# bredtoob.net
KiCad netlist of a schematic drawn in EAGLE
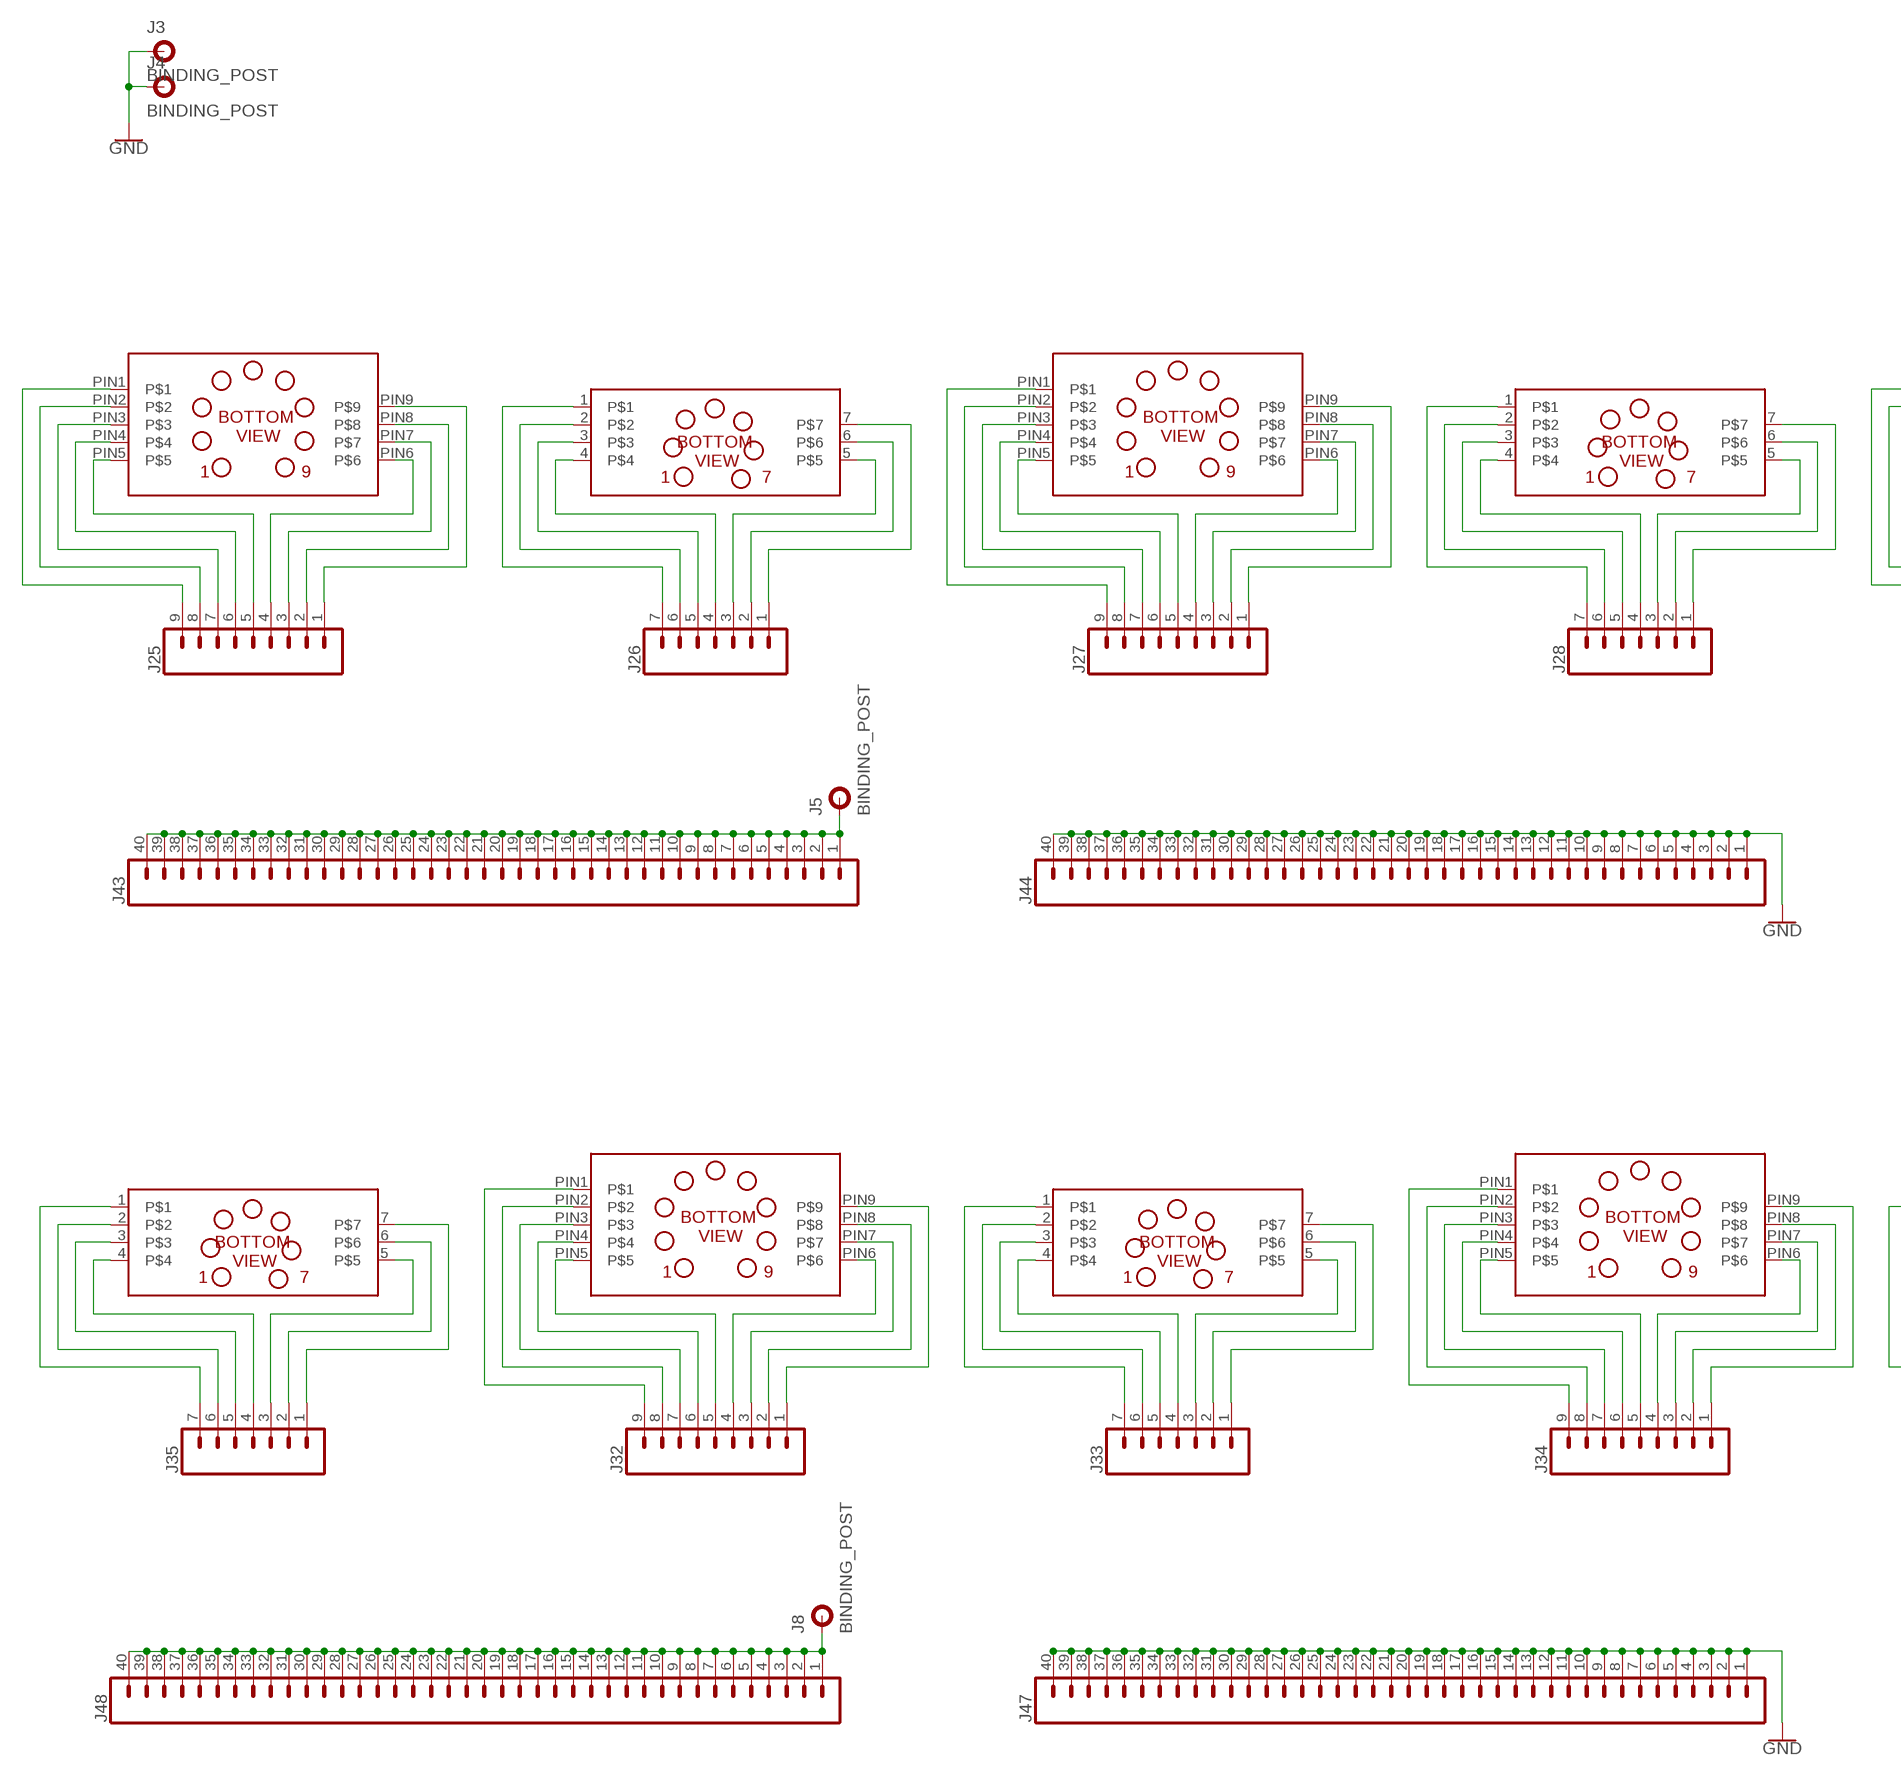
[diagram p0: schematic, sheet 1, part 1 of 2]
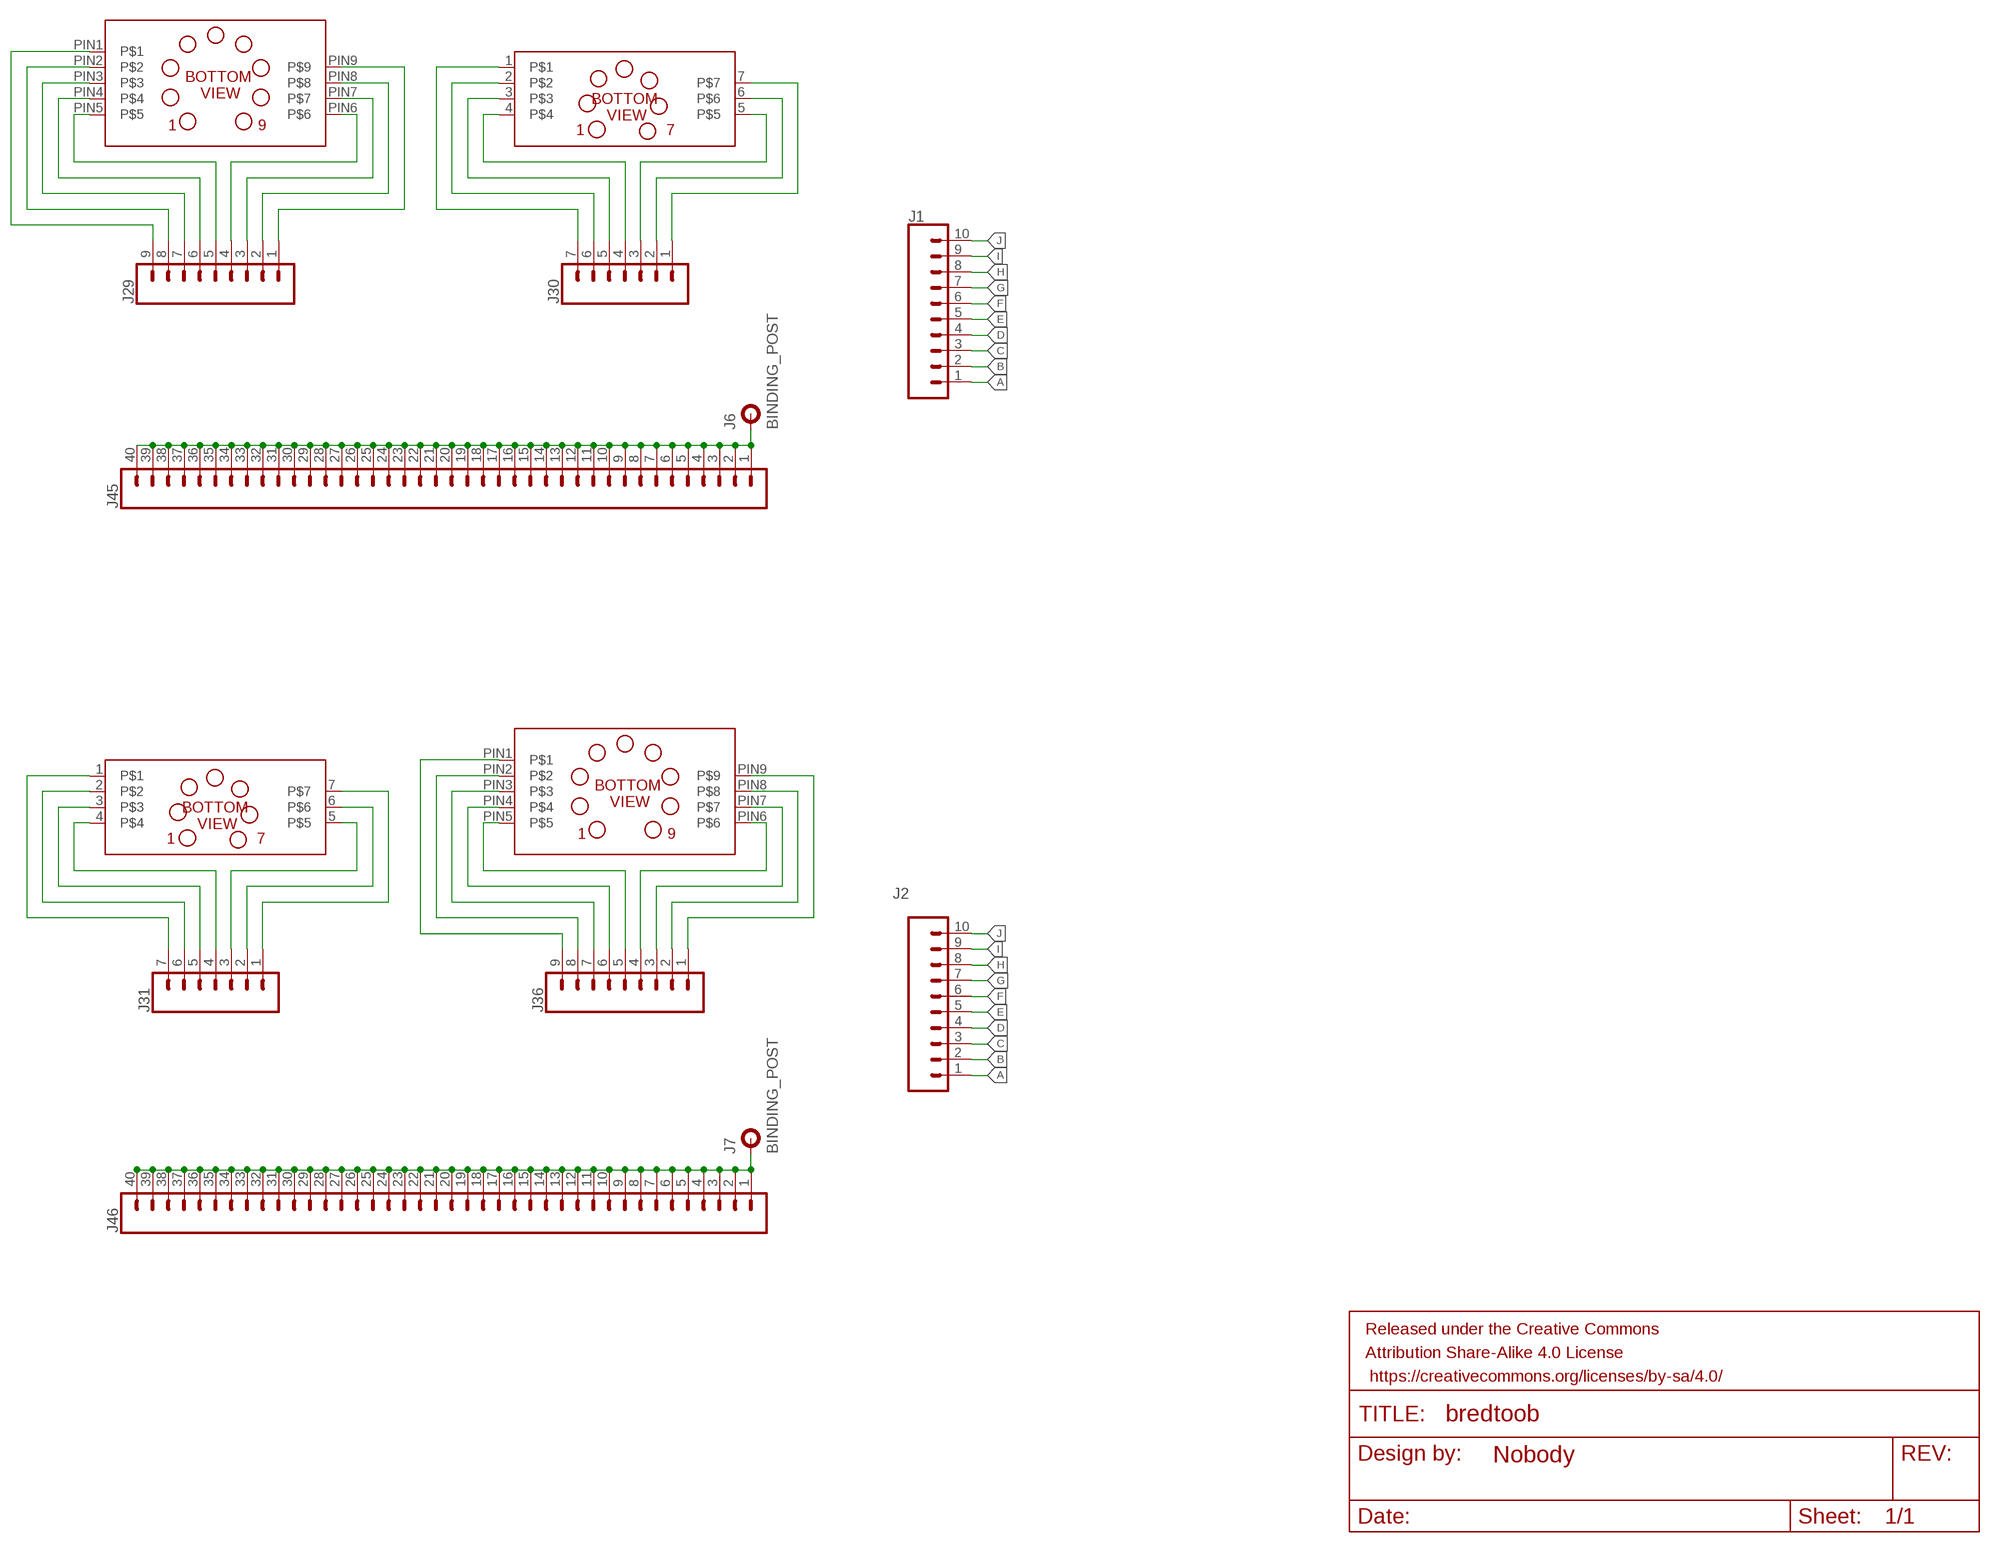
[diagram p1: schematic, sheet 1, part 2 of 2]

(export (version "E")
  (design (tool "Eeschema 10.0.6"))
  (components
    (comp (ref "FRAME1")
      (value "FRAME-LETTERNO_PACKAGE")
      (footprint "eagle-import:DUMMY")
      (fields (field (name "DESIGNER") "Nobody"))
      (libsource (lib "eagle-import") (part "FRAME-LETTERNO_PACKAGE"))
    )
    (comp (ref "J1")
      (value "CONN_10NO_SILK_PTH_FEMALE")
      (footprint "eagle-import:1X10_NO_SILK")
      (libsource (lib "eagle-import") (part "CONN_10NO_SILK_PTH_FEMALE"))
    )
    (comp (ref "J2")
      (value "CONN_10NO_SILK_PTH_FEMALE")
      (footprint "eagle-import:1X10_NO_SILK")
      (libsource (lib "eagle-import") (part "CONN_10NO_SILK_PTH_FEMALE"))
    )
    (comp (ref "J3")
      (value "BINDING_POST")
      (footprint "eagle-import:BINDING_POST")
      (libsource (lib "eagle-import") (part "BINDING_POST"))
    )
    (comp (ref "J4")
      (value "BINDING_POST")
      (footprint "eagle-import:BINDING_POST")
      (libsource (lib "eagle-import") (part "BINDING_POST"))
    )
    (comp (ref "J5")
      (value "BINDING_POST")
      (footprint "eagle-import:BINDING_POST")
      (libsource (lib "eagle-import") (part "BINDING_POST"))
    )
    (comp (ref "J6")
      (value "BINDING_POST")
      (footprint "eagle-import:BINDING_POST")
      (libsource (lib "eagle-import") (part "BINDING_POST"))
    )
    (comp (ref "J7")
      (value "BINDING_POST")
      (footprint "eagle-import:BINDING_POST")
      (libsource (lib "eagle-import") (part "BINDING_POST"))
    )
    (comp (ref "J8")
      (value "BINDING_POST")
      (footprint "eagle-import:BINDING_POST")
      (libsource (lib "eagle-import") (part "BINDING_POST"))
    )
    (comp (ref "J25")
      (value "CONN_09")
      (footprint "eagle-import:1X09")
      (libsource (lib "eagle-import") (part "CONN_09"))
    )
    (comp (ref "J26")
      (value "CONN_07NO_SILK")
      (footprint "eagle-import:1X07_NO_SILK")
      (libsource (lib "eagle-import") (part "CONN_07NO_SILK"))
    )
    (comp (ref "J27")
      (value "CONN_09")
      (footprint "eagle-import:1X09")
      (libsource (lib "eagle-import") (part "CONN_09"))
    )
    (comp (ref "J28")
      (value "CONN_07NO_SILK")
      (footprint "eagle-import:1X07_NO_SILK")
      (libsource (lib "eagle-import") (part "CONN_07NO_SILK"))
    )
    (comp (ref "J29")
      (value "CONN_09")
      (footprint "eagle-import:1X09")
      (libsource (lib "eagle-import") (part "CONN_09"))
    )
    (comp (ref "J30")
      (value "CONN_07NO_SILK")
      (footprint "eagle-import:1X07_NO_SILK")
      (libsource (lib "eagle-import") (part "CONN_07NO_SILK"))
    )
    (comp (ref "J31")
      (value "CONN_07NO_SILK")
      (footprint "eagle-import:1X07_NO_SILK")
      (libsource (lib "eagle-import") (part "CONN_07NO_SILK"))
    )
    (comp (ref "J32")
      (value "CONN_09")
      (footprint "eagle-import:1X09")
      (libsource (lib "eagle-import") (part "CONN_09"))
    )
    (comp (ref "J33")
      (value "CONN_07NO_SILK")
      (footprint "eagle-import:1X07_NO_SILK")
      (libsource (lib "eagle-import") (part "CONN_07NO_SILK"))
    )
    (comp (ref "J34")
      (value "CONN_09")
      (footprint "eagle-import:1X09")
      (libsource (lib "eagle-import") (part "CONN_09"))
    )
    (comp (ref "J35")
      (value "CONN_07NO_SILK")
      (footprint "eagle-import:1X07_NO_SILK")
      (libsource (lib "eagle-import") (part "CONN_07NO_SILK"))
    )
    (comp (ref "J36")
      (value "CONN_09")
      (footprint "eagle-import:1X09")
      (libsource (lib "eagle-import") (part "CONN_09"))
    )
    (comp (ref "J43")
      (value "CONN_40")
      (footprint "eagle-import:1X40")
      (libsource (lib "eagle-import") (part "CONN_40"))
    )
    (comp (ref "J44")
      (value "CONN_40")
      (footprint "eagle-import:1X40")
      (libsource (lib "eagle-import") (part "CONN_40"))
    )
    (comp (ref "J45")
      (value "CONN_40")
      (footprint "eagle-import:1X40")
      (libsource (lib "eagle-import") (part "CONN_40"))
    )
    (comp (ref "J46")
      (value "CONN_40")
      (footprint "eagle-import:1X40")
      (libsource (lib "eagle-import") (part "CONN_40"))
    )
    (comp (ref "J47")
      (value "CONN_40")
      (footprint "eagle-import:1X40")
      (libsource (lib "eagle-import") (part "CONN_40"))
    )
    (comp (ref "J48")
      (value "CONN_40")
      (footprint "eagle-import:1X40")
      (libsource (lib "eagle-import") (part "CONN_40"))
    )
    (comp (ref "U$1")
      (value "9PINMINI")
      (footprint "eagle-import:9-PIN-MINIATURE")
      (libsource (lib "eagle-import") (part "9PINMINI"))
    )
    (comp (ref "U$2")
      (value "7PINMINI")
      (footprint "eagle-import:7-PIN-MINIATURE(B7G)")
      (libsource (lib "eagle-import") (part "7PINMINI"))
    )
    (comp (ref "U$3")
      (value "9PINMINI")
      (footprint "eagle-import:9-PIN-MINIATURE")
      (libsource (lib "eagle-import") (part "9PINMINI"))
    )
    (comp (ref "U$4")
      (value "7PINMINI")
      (footprint "eagle-import:7-PIN-MINIATURE(B7G)")
      (libsource (lib "eagle-import") (part "7PINMINI"))
    )
    (comp (ref "U$5")
      (value "9PINMINI")
      (footprint "eagle-import:9-PIN-MINIATURE")
      (libsource (lib "eagle-import") (part "9PINMINI"))
    )
    (comp (ref "U$6")
      (value "7PINMINI")
      (footprint "eagle-import:7-PIN-MINIATURE(B7G)")
      (libsource (lib "eagle-import") (part "7PINMINI"))
    )
    (comp (ref "U$7")
      (value "7PINMINI")
      (footprint "eagle-import:7-PIN-MINIATURE(B7G)")
      (libsource (lib "eagle-import") (part "7PINMINI"))
    )
    (comp (ref "U$8")
      (value "9PINMINI")
      (footprint "eagle-import:9-PIN-MINIATURE")
      (libsource (lib "eagle-import") (part "9PINMINI"))
    )
    (comp (ref "U$9")
      (value "7PINMINI")
      (footprint "eagle-import:7-PIN-MINIATURE(B7G)")
      (libsource (lib "eagle-import") (part "7PINMINI"))
    )
    (comp (ref "U$10")
      (value "9PINMINI")
      (footprint "eagle-import:9-PIN-MINIATURE")
      (libsource (lib "eagle-import") (part "9PINMINI"))
    )
    (comp (ref "U$11")
      (value "7PINMINI")
      (footprint "eagle-import:7-PIN-MINIATURE(B7G)")
      (libsource (lib "eagle-import") (part "7PINMINI"))
    )
    (comp (ref "U$12")
      (value "9PINMINI")
      (footprint "eagle-import:9-PIN-MINIATURE")
      (libsource (lib "eagle-import") (part "9PINMINI"))
    )
  )
  (nets
    (net (code "1") (name "A") (class "Default")
      (node (ref "J1") (pin "1") (pinfunction "1_1") (pintype "passive"))
      (node (ref "J2") (pin "1") (pinfunction "1_1") (pintype "passive"))
    )
    (net (code "2") (name "B") (class "Default")
      (node (ref "J1") (pin "2") (pinfunction "2_2") (pintype "passive"))
      (node (ref "J2") (pin "2") (pinfunction "2_2") (pintype "passive"))
    )
    (net (code "3") (name "C") (class "Default")
      (node (ref "J1") (pin "3") (pinfunction "3_3") (pintype "passive"))
      (node (ref "J2") (pin "3") (pinfunction "3_3") (pintype "passive"))
    )
    (net (code "4") (name "D") (class "Default")
      (node (ref "J1") (pin "4") (pinfunction "4_4") (pintype "passive"))
      (node (ref "J2") (pin "4") (pinfunction "4_4") (pintype "passive"))
    )
    (net (code "5") (name "E") (class "Default")
      (node (ref "J1") (pin "5") (pinfunction "5_5") (pintype "passive"))
      (node (ref "J2") (pin "5") (pinfunction "5_5") (pintype "passive"))
    )
    (net (code "6") (name "F") (class "Default")
      (node (ref "J1") (pin "6") (pinfunction "6_6") (pintype "passive"))
      (node (ref "J2") (pin "6") (pinfunction "6_6") (pintype "passive"))
    )
    (net (code "7") (name "G") (class "Default")
      (node (ref "J1") (pin "7") (pinfunction "7_7") (pintype "passive"))
      (node (ref "J2") (pin "7") (pinfunction "7_7") (pintype "passive"))
    )
    (net (code "8") (name "GND") (class "Default")
      (node (ref "J3") (pin "P$1") (pinfunction "P$1_P$1") (pintype "bidirectional"))
      (node (ref "J4") (pin "P$1") (pinfunction "P$1_P$1") (pintype "bidirectional"))
      (node (ref "J44") (pin "1") (pinfunction "1_1") (pintype "passive"))
      (node (ref "J44") (pin "10") (pinfunction "10_10") (pintype "passive"))
      (node (ref "J44") (pin "11") (pinfunction "11_11") (pintype "passive"))
      (node (ref "J44") (pin "12") (pinfunction "12_12") (pintype "passive"))
      (node (ref "J44") (pin "13") (pinfunction "13_13") (pintype "passive"))
      (node (ref "J44") (pin "14") (pinfunction "14_14") (pintype "passive"))
      (node (ref "J44") (pin "15") (pinfunction "15_15") (pintype "passive"))
      (node (ref "J44") (pin "16") (pinfunction "16_16") (pintype "passive"))
      (node (ref "J44") (pin "17") (pinfunction "17_17") (pintype "passive"))
      (node (ref "J44") (pin "18") (pinfunction "18_18") (pintype "passive"))
      (node (ref "J44") (pin "19") (pinfunction "19_19") (pintype "passive"))
      (node (ref "J44") (pin "2") (pinfunction "2_2") (pintype "passive"))
      (node (ref "J44") (pin "20") (pinfunction "20_20") (pintype "passive"))
      (node (ref "J44") (pin "21") (pinfunction "21_21") (pintype "passive"))
      (node (ref "J44") (pin "22") (pinfunction "22_22") (pintype "passive"))
      (node (ref "J44") (pin "23") (pinfunction "23_23") (pintype "passive"))
      (node (ref "J44") (pin "24") (pinfunction "24_24") (pintype "passive"))
      (node (ref "J44") (pin "25") (pinfunction "25_25") (pintype "passive"))
      (node (ref "J44") (pin "26") (pinfunction "26_26") (pintype "passive"))
      (node (ref "J44") (pin "27") (pinfunction "27_27") (pintype "passive"))
      (node (ref "J44") (pin "28") (pinfunction "28_28") (pintype "passive"))
      (node (ref "J44") (pin "29") (pinfunction "29_29") (pintype "passive"))
      (node (ref "J44") (pin "3") (pinfunction "3_3") (pintype "passive"))
      (node (ref "J44") (pin "30") (pinfunction "30_30") (pintype "passive"))
      (node (ref "J44") (pin "31") (pinfunction "31_31") (pintype "passive"))
      (node (ref "J44") (pin "32") (pinfunction "32_32") (pintype "passive"))
      (node (ref "J44") (pin "33") (pinfunction "33_33") (pintype "passive"))
      (node (ref "J44") (pin "34") (pinfunction "34_34") (pintype "passive"))
      (node (ref "J44") (pin "35") (pinfunction "35_35") (pintype "passive"))
      (node (ref "J44") (pin "36") (pinfunction "36_36") (pintype "passive"))
      (node (ref "J44") (pin "37") (pinfunction "37_37") (pintype "passive"))
      (node (ref "J44") (pin "38") (pinfunction "38_38") (pintype "passive"))
      (node (ref "J44") (pin "39") (pinfunction "39_39") (pintype "passive"))
      (node (ref "J44") (pin "4") (pinfunction "4_4") (pintype "passive"))
      (node (ref "J44") (pin "40") (pinfunction "40_40") (pintype "passive"))
      (node (ref "J44") (pin "5") (pinfunction "5_5") (pintype "passive"))
      (node (ref "J44") (pin "6") (pinfunction "6_6") (pintype "passive"))
      (node (ref "J44") (pin "7") (pinfunction "7_7") (pintype "passive"))
      (node (ref "J44") (pin "8") (pinfunction "8_8") (pintype "passive"))
      (node (ref "J44") (pin "9") (pinfunction "9_9") (pintype "passive"))
      (node (ref "J47") (pin "1") (pinfunction "1_1") (pintype "passive"))
      (node (ref "J47") (pin "10") (pinfunction "10_10") (pintype "passive"))
      (node (ref "J47") (pin "11") (pinfunction "11_11") (pintype "passive"))
      (node (ref "J47") (pin "12") (pinfunction "12_12") (pintype "passive"))
      (node (ref "J47") (pin "13") (pinfunction "13_13") (pintype "passive"))
      (node (ref "J47") (pin "14") (pinfunction "14_14") (pintype "passive"))
      (node (ref "J47") (pin "15") (pinfunction "15_15") (pintype "passive"))
      (node (ref "J47") (pin "16") (pinfunction "16_16") (pintype "passive"))
      (node (ref "J47") (pin "17") (pinfunction "17_17") (pintype "passive"))
      (node (ref "J47") (pin "18") (pinfunction "18_18") (pintype "passive"))
      (node (ref "J47") (pin "19") (pinfunction "19_19") (pintype "passive"))
      (node (ref "J47") (pin "2") (pinfunction "2_2") (pintype "passive"))
      (node (ref "J47") (pin "20") (pinfunction "20_20") (pintype "passive"))
      (node (ref "J47") (pin "21") (pinfunction "21_21") (pintype "passive"))
      (node (ref "J47") (pin "22") (pinfunction "22_22") (pintype "passive"))
      (node (ref "J47") (pin "23") (pinfunction "23_23") (pintype "passive"))
      (node (ref "J47") (pin "24") (pinfunction "24_24") (pintype "passive"))
      (node (ref "J47") (pin "25") (pinfunction "25_25") (pintype "passive"))
      (node (ref "J47") (pin "26") (pinfunction "26_26") (pintype "passive"))
      (node (ref "J47") (pin "27") (pinfunction "27_27") (pintype "passive"))
      (node (ref "J47") (pin "28") (pinfunction "28_28") (pintype "passive"))
      (node (ref "J47") (pin "29") (pinfunction "29_29") (pintype "passive"))
      (node (ref "J47") (pin "3") (pinfunction "3_3") (pintype "passive"))
      (node (ref "J47") (pin "30") (pinfunction "30_30") (pintype "passive"))
      (node (ref "J47") (pin "31") (pinfunction "31_31") (pintype "passive"))
      (node (ref "J47") (pin "32") (pinfunction "32_32") (pintype "passive"))
      (node (ref "J47") (pin "33") (pinfunction "33_33") (pintype "passive"))
      (node (ref "J47") (pin "34") (pinfunction "34_34") (pintype "passive"))
      (node (ref "J47") (pin "35") (pinfunction "35_35") (pintype "passive"))
      (node (ref "J47") (pin "36") (pinfunction "36_36") (pintype "passive"))
      (node (ref "J47") (pin "37") (pinfunction "37_37") (pintype "passive"))
      (node (ref "J47") (pin "38") (pinfunction "38_38") (pintype "passive"))
      (node (ref "J47") (pin "39") (pinfunction "39_39") (pintype "passive"))
      (node (ref "J47") (pin "4") (pinfunction "4_4") (pintype "passive"))
      (node (ref "J47") (pin "40") (pinfunction "40_40") (pintype "passive"))
      (node (ref "J47") (pin "5") (pinfunction "5_5") (pintype "passive"))
      (node (ref "J47") (pin "6") (pinfunction "6_6") (pintype "passive"))
      (node (ref "J47") (pin "7") (pinfunction "7_7") (pintype "passive"))
      (node (ref "J47") (pin "8") (pinfunction "8_8") (pintype "passive"))
      (node (ref "J47") (pin "9") (pinfunction "9_9") (pintype "passive"))
    )
    (net (code "9") (name "H") (class "Default")
      (node (ref "J1") (pin "8") (pinfunction "8_8") (pintype "passive"))
      (node (ref "J2") (pin "8") (pinfunction "8_8") (pintype "passive"))
    )
    (net (code "10") (name "I") (class "Default")
      (node (ref "J1") (pin "9") (pinfunction "9_9") (pintype "passive"))
      (node (ref "J2") (pin "9") (pinfunction "9_9") (pintype "passive"))
    )
    (net (code "11") (name "J") (class "Default")
      (node (ref "J1") (pin "10") (pinfunction "10_10") (pintype "passive"))
      (node (ref "J2") (pin "10") (pinfunction "10_10") (pintype "passive"))
    )
    (net (code "12") (name "Net-(J43-Pad1)") (class "Default")
      (node (ref "J43") (pin "1") (pinfunction "1_1") (pintype "passive"))
      (node (ref "J43") (pin "10") (pinfunction "10_10") (pintype "passive"))
      (node (ref "J43") (pin "11") (pinfunction "11_11") (pintype "passive"))
      (node (ref "J43") (pin "12") (pinfunction "12_12") (pintype "passive"))
      (node (ref "J43") (pin "13") (pinfunction "13_13") (pintype "passive"))
      (node (ref "J43") (pin "14") (pinfunction "14_14") (pintype "passive"))
      (node (ref "J43") (pin "15") (pinfunction "15_15") (pintype "passive"))
      (node (ref "J43") (pin "16") (pinfunction "16_16") (pintype "passive"))
      (node (ref "J43") (pin "17") (pinfunction "17_17") (pintype "passive"))
      (node (ref "J43") (pin "18") (pinfunction "18_18") (pintype "passive"))
      (node (ref "J43") (pin "19") (pinfunction "19_19") (pintype "passive"))
      (node (ref "J43") (pin "2") (pinfunction "2_2") (pintype "passive"))
      (node (ref "J43") (pin "20") (pinfunction "20_20") (pintype "passive"))
      (node (ref "J43") (pin "21") (pinfunction "21_21") (pintype "passive"))
      (node (ref "J43") (pin "22") (pinfunction "22_22") (pintype "passive"))
      (node (ref "J43") (pin "23") (pinfunction "23_23") (pintype "passive"))
      (node (ref "J43") (pin "24") (pinfunction "24_24") (pintype "passive"))
      (node (ref "J43") (pin "25") (pinfunction "25_25") (pintype "passive"))
      (node (ref "J43") (pin "26") (pinfunction "26_26") (pintype "passive"))
      (node (ref "J43") (pin "27") (pinfunction "27_27") (pintype "passive"))
      (node (ref "J43") (pin "28") (pinfunction "28_28") (pintype "passive"))
      (node (ref "J43") (pin "29") (pinfunction "29_29") (pintype "passive"))
      (node (ref "J43") (pin "3") (pinfunction "3_3") (pintype "passive"))
      (node (ref "J43") (pin "30") (pinfunction "30_30") (pintype "passive"))
      (node (ref "J43") (pin "31") (pinfunction "31_31") (pintype "passive"))
      (node (ref "J43") (pin "32") (pinfunction "32_32") (pintype "passive"))
      (node (ref "J43") (pin "33") (pinfunction "33_33") (pintype "passive"))
      (node (ref "J43") (pin "34") (pinfunction "34_34") (pintype "passive"))
      (node (ref "J43") (pin "35") (pinfunction "35_35") (pintype "passive"))
      (node (ref "J43") (pin "36") (pinfunction "36_36") (pintype "passive"))
      (node (ref "J43") (pin "37") (pinfunction "37_37") (pintype "passive"))
      (node (ref "J43") (pin "38") (pinfunction "38_38") (pintype "passive"))
      (node (ref "J43") (pin "39") (pinfunction "39_39") (pintype "passive"))
      (node (ref "J43") (pin "4") (pinfunction "4_4") (pintype "passive"))
      (node (ref "J43") (pin "40") (pinfunction "40_40") (pintype "passive"))
      (node (ref "J43") (pin "5") (pinfunction "5_5") (pintype "passive"))
      (node (ref "J43") (pin "6") (pinfunction "6_6") (pintype "passive"))
      (node (ref "J43") (pin "7") (pinfunction "7_7") (pintype "passive"))
      (node (ref "J43") (pin "8") (pinfunction "8_8") (pintype "passive"))
      (node (ref "J43") (pin "9") (pinfunction "9_9") (pintype "passive"))
      (node (ref "J5") (pin "P$1") (pinfunction "P$1_P$1") (pintype "bidirectional"))
    )
    (net (code "13") (name "Net-(J45-Pad1)") (class "Default")
      (node (ref "J45") (pin "1") (pinfunction "1_1") (pintype "passive"))
      (node (ref "J45") (pin "10") (pinfunction "10_10") (pintype "passive"))
      (node (ref "J45") (pin "11") (pinfunction "11_11") (pintype "passive"))
      (node (ref "J45") (pin "12") (pinfunction "12_12") (pintype "passive"))
      (node (ref "J45") (pin "13") (pinfunction "13_13") (pintype "passive"))
      (node (ref "J45") (pin "14") (pinfunction "14_14") (pintype "passive"))
      (node (ref "J45") (pin "15") (pinfunction "15_15") (pintype "passive"))
      (node (ref "J45") (pin "16") (pinfunction "16_16") (pintype "passive"))
      (node (ref "J45") (pin "17") (pinfunction "17_17") (pintype "passive"))
      (node (ref "J45") (pin "18") (pinfunction "18_18") (pintype "passive"))
      (node (ref "J45") (pin "19") (pinfunction "19_19") (pintype "passive"))
      (node (ref "J45") (pin "2") (pinfunction "2_2") (pintype "passive"))
      (node (ref "J45") (pin "20") (pinfunction "20_20") (pintype "passive"))
      (node (ref "J45") (pin "21") (pinfunction "21_21") (pintype "passive"))
      (node (ref "J45") (pin "22") (pinfunction "22_22") (pintype "passive"))
      (node (ref "J45") (pin "23") (pinfunction "23_23") (pintype "passive"))
      (node (ref "J45") (pin "24") (pinfunction "24_24") (pintype "passive"))
      (node (ref "J45") (pin "25") (pinfunction "25_25") (pintype "passive"))
      (node (ref "J45") (pin "26") (pinfunction "26_26") (pintype "passive"))
      (node (ref "J45") (pin "27") (pinfunction "27_27") (pintype "passive"))
      (node (ref "J45") (pin "28") (pinfunction "28_28") (pintype "passive"))
      (node (ref "J45") (pin "29") (pinfunction "29_29") (pintype "passive"))
      (node (ref "J45") (pin "3") (pinfunction "3_3") (pintype "passive"))
      (node (ref "J45") (pin "30") (pinfunction "30_30") (pintype "passive"))
      (node (ref "J45") (pin "31") (pinfunction "31_31") (pintype "passive"))
      (node (ref "J45") (pin "32") (pinfunction "32_32") (pintype "passive"))
      (node (ref "J45") (pin "33") (pinfunction "33_33") (pintype "passive"))
      (node (ref "J45") (pin "34") (pinfunction "34_34") (pintype "passive"))
      (node (ref "J45") (pin "35") (pinfunction "35_35") (pintype "passive"))
      (node (ref "J45") (pin "36") (pinfunction "36_36") (pintype "passive"))
      (node (ref "J45") (pin "37") (pinfunction "37_37") (pintype "passive"))
      (node (ref "J45") (pin "38") (pinfunction "38_38") (pintype "passive"))
      (node (ref "J45") (pin "39") (pinfunction "39_39") (pintype "passive"))
      (node (ref "J45") (pin "4") (pinfunction "4_4") (pintype "passive"))
      (node (ref "J45") (pin "40") (pinfunction "40_40") (pintype "passive"))
      (node (ref "J45") (pin "5") (pinfunction "5_5") (pintype "passive"))
      (node (ref "J45") (pin "6") (pinfunction "6_6") (pintype "passive"))
      (node (ref "J45") (pin "7") (pinfunction "7_7") (pintype "passive"))
      (node (ref "J45") (pin "8") (pinfunction "8_8") (pintype "passive"))
      (node (ref "J45") (pin "9") (pinfunction "9_9") (pintype "passive"))
      (node (ref "J6") (pin "P$1") (pinfunction "P$1_P$1") (pintype "bidirectional"))
    )
    (net (code "14") (name "Net-(J46-Pad1)") (class "Default")
      (node (ref "J46") (pin "1") (pinfunction "1_1") (pintype "passive"))
      (node (ref "J46") (pin "10") (pinfunction "10_10") (pintype "passive"))
      (node (ref "J46") (pin "11") (pinfunction "11_11") (pintype "passive"))
      (node (ref "J46") (pin "12") (pinfunction "12_12") (pintype "passive"))
      (node (ref "J46") (pin "13") (pinfunction "13_13") (pintype "passive"))
      (node (ref "J46") (pin "14") (pinfunction "14_14") (pintype "passive"))
      (node (ref "J46") (pin "15") (pinfunction "15_15") (pintype "passive"))
      (node (ref "J46") (pin "16") (pinfunction "16_16") (pintype "passive"))
      (node (ref "J46") (pin "17") (pinfunction "17_17") (pintype "passive"))
      (node (ref "J46") (pin "18") (pinfunction "18_18") (pintype "passive"))
      (node (ref "J46") (pin "19") (pinfunction "19_19") (pintype "passive"))
      (node (ref "J46") (pin "2") (pinfunction "2_2") (pintype "passive"))
      (node (ref "J46") (pin "20") (pinfunction "20_20") (pintype "passive"))
      (node (ref "J46") (pin "21") (pinfunction "21_21") (pintype "passive"))
      (node (ref "J46") (pin "22") (pinfunction "22_22") (pintype "passive"))
      (node (ref "J46") (pin "23") (pinfunction "23_23") (pintype "passive"))
      (node (ref "J46") (pin "24") (pinfunction "24_24") (pintype "passive"))
      (node (ref "J46") (pin "25") (pinfunction "25_25") (pintype "passive"))
      (node (ref "J46") (pin "26") (pinfunction "26_26") (pintype "passive"))
      (node (ref "J46") (pin "27") (pinfunction "27_27") (pintype "passive"))
      (node (ref "J46") (pin "28") (pinfunction "28_28") (pintype "passive"))
      (node (ref "J46") (pin "29") (pinfunction "29_29") (pintype "passive"))
      (node (ref "J46") (pin "3") (pinfunction "3_3") (pintype "passive"))
      (node (ref "J46") (pin "30") (pinfunction "30_30") (pintype "passive"))
      (node (ref "J46") (pin "31") (pinfunction "31_31") (pintype "passive"))
      (node (ref "J46") (pin "32") (pinfunction "32_32") (pintype "passive"))
      (node (ref "J46") (pin "33") (pinfunction "33_33") (pintype "passive"))
      (node (ref "J46") (pin "34") (pinfunction "34_34") (pintype "passive"))
      (node (ref "J46") (pin "35") (pinfunction "35_35") (pintype "passive"))
      (node (ref "J46") (pin "36") (pinfunction "36_36") (pintype "passive"))
      (node (ref "J46") (pin "37") (pinfunction "37_37") (pintype "passive"))
      (node (ref "J46") (pin "38") (pinfunction "38_38") (pintype "passive"))
      (node (ref "J46") (pin "39") (pinfunction "39_39") (pintype "passive"))
      (node (ref "J46") (pin "4") (pinfunction "4_4") (pintype "passive"))
      (node (ref "J46") (pin "40") (pinfunction "40_40") (pintype "passive"))
      (node (ref "J46") (pin "5") (pinfunction "5_5") (pintype "passive"))
      (node (ref "J46") (pin "6") (pinfunction "6_6") (pintype "passive"))
      (node (ref "J46") (pin "7") (pinfunction "7_7") (pintype "passive"))
      (node (ref "J46") (pin "8") (pinfunction "8_8") (pintype "passive"))
      (node (ref "J46") (pin "9") (pinfunction "9_9") (pintype "passive"))
      (node (ref "J7") (pin "P$1") (pinfunction "P$1_P$1") (pintype "bidirectional"))
    )
    (net (code "15") (name "Net-(J48-Pad1)") (class "Default")
      (node (ref "J48") (pin "1") (pinfunction "1_1") (pintype "passive"))
      (node (ref "J48") (pin "10") (pinfunction "10_10") (pintype "passive"))
      (node (ref "J48") (pin "11") (pinfunction "11_11") (pintype "passive"))
      (node (ref "J48") (pin "12") (pinfunction "12_12") (pintype "passive"))
      (node (ref "J48") (pin "13") (pinfunction "13_13") (pintype "passive"))
      (node (ref "J48") (pin "14") (pinfunction "14_14") (pintype "passive"))
      (node (ref "J48") (pin "15") (pinfunction "15_15") (pintype "passive"))
      (node (ref "J48") (pin "16") (pinfunction "16_16") (pintype "passive"))
      (node (ref "J48") (pin "17") (pinfunction "17_17") (pintype "passive"))
      (node (ref "J48") (pin "18") (pinfunction "18_18") (pintype "passive"))
      (node (ref "J48") (pin "19") (pinfunction "19_19") (pintype "passive"))
      (node (ref "J48") (pin "2") (pinfunction "2_2") (pintype "passive"))
      (node (ref "J48") (pin "20") (pinfunction "20_20") (pintype "passive"))
      (node (ref "J48") (pin "21") (pinfunction "21_21") (pintype "passive"))
      (node (ref "J48") (pin "22") (pinfunction "22_22") (pintype "passive"))
      (node (ref "J48") (pin "23") (pinfunction "23_23") (pintype "passive"))
      (node (ref "J48") (pin "24") (pinfunction "24_24") (pintype "passive"))
      (node (ref "J48") (pin "25") (pinfunction "25_25") (pintype "passive"))
      (node (ref "J48") (pin "26") (pinfunction "26_26") (pintype "passive"))
      (node (ref "J48") (pin "27") (pinfunction "27_27") (pintype "passive"))
      (node (ref "J48") (pin "28") (pinfunction "28_28") (pintype "passive"))
      (node (ref "J48") (pin "29") (pinfunction "29_29") (pintype "passive"))
      (node (ref "J48") (pin "3") (pinfunction "3_3") (pintype "passive"))
      (node (ref "J48") (pin "30") (pinfunction "30_30") (pintype "passive"))
      (node (ref "J48") (pin "31") (pinfunction "31_31") (pintype "passive"))
      (node (ref "J48") (pin "32") (pinfunction "32_32") (pintype "passive"))
      (node (ref "J48") (pin "33") (pinfunction "33_33") (pintype "passive"))
      (node (ref "J48") (pin "34") (pinfunction "34_34") (pintype "passive"))
      (node (ref "J48") (pin "35") (pinfunction "35_35") (pintype "passive"))
      (node (ref "J48") (pin "36") (pinfunction "36_36") (pintype "passive"))
      (node (ref "J48") (pin "37") (pinfunction "37_37") (pintype "passive"))
      (node (ref "J48") (pin "38") (pinfunction "38_38") (pintype "passive"))
      (node (ref "J48") (pin "39") (pinfunction "39_39") (pintype "passive"))
      (node (ref "J48") (pin "4") (pinfunction "4_4") (pintype "passive"))
      (node (ref "J48") (pin "40") (pinfunction "40_40") (pintype "passive"))
      (node (ref "J48") (pin "5") (pinfunction "5_5") (pintype "passive"))
      (node (ref "J48") (pin "6") (pinfunction "6_6") (pintype "passive"))
      (node (ref "J48") (pin "7") (pinfunction "7_7") (pintype "passive"))
      (node (ref "J48") (pin "8") (pinfunction "8_8") (pintype "passive"))
      (node (ref "J48") (pin "9") (pinfunction "9_9") (pintype "passive"))
      (node (ref "J8") (pin "P$1") (pinfunction "P$1_P$1") (pintype "bidirectional"))
    )
    (net (code "16") (name "Net-(U$1-P$1)") (class "Default")
      (node (ref "J25") (pin "9") (pinfunction "9_9") (pintype "passive"))
      (node (ref "U$1") (pin "PIN1") (pinfunction "P$1_PIN1") (pintype "bidirectional"))
    )
    (net (code "17") (name "Net-(U$1-P$2)") (class "Default")
      (node (ref "J25") (pin "8") (pinfunction "8_8") (pintype "passive"))
      (node (ref "U$1") (pin "PIN2") (pinfunction "P$2_PIN2") (pintype "bidirectional"))
    )
    (net (code "18") (name "Net-(U$1-P$3)") (class "Default")
      (node (ref "J25") (pin "7") (pinfunction "7_7") (pintype "passive"))
      (node (ref "U$1") (pin "PIN3") (pinfunction "P$3_PIN3") (pintype "bidirectional"))
    )
    (net (code "19") (name "Net-(U$1-P$4)") (class "Default")
      (node (ref "J25") (pin "6") (pinfunction "6_6") (pintype "passive"))
      (node (ref "U$1") (pin "PIN4") (pinfunction "P$4_PIN4") (pintype "bidirectional"))
    )
    (net (code "20") (name "Net-(U$1-P$5)") (class "Default")
      (node (ref "J25") (pin "5") (pinfunction "5_5") (pintype "passive"))
      (node (ref "U$1") (pin "PIN5") (pinfunction "P$5_PIN5") (pintype "bidirectional"))
    )
    (net (code "21") (name "Net-(U$1-P$6)") (class "Default")
      (node (ref "J25") (pin "4") (pinfunction "4_4") (pintype "passive"))
      (node (ref "U$1") (pin "PIN6") (pinfunction "P$6_PIN6") (pintype "bidirectional"))
    )
    (net (code "22") (name "Net-(U$1-P$7)") (class "Default")
      (node (ref "J25") (pin "3") (pinfunction "3_3") (pintype "passive"))
      (node (ref "U$1") (pin "PIN7") (pinfunction "P$7_PIN7") (pintype "bidirectional"))
    )
    (net (code "23") (name "Net-(U$1-P$8)") (class "Default")
      (node (ref "J25") (pin "2") (pinfunction "2_2") (pintype "passive"))
      (node (ref "U$1") (pin "PIN8") (pinfunction "P$8_PIN8") (pintype "bidirectional"))
    )
    (net (code "24") (name "Net-(U$1-P$9)") (class "Default")
      (node (ref "J25") (pin "1") (pinfunction "1_1") (pintype "passive"))
      (node (ref "U$1") (pin "PIN9") (pinfunction "P$9_PIN9") (pintype "bidirectional"))
    )
    (net (code "25") (name "Net-(U$2-P$1)") (class "Default")
      (node (ref "J26") (pin "7") (pinfunction "7_7") (pintype "passive"))
      (node (ref "U$2") (pin "1") (pinfunction "P$1_1") (pintype "bidirectional"))
    )
    (net (code "26") (name "Net-(U$2-P$2)") (class "Default")
      (node (ref "J26") (pin "6") (pinfunction "6_6") (pintype "passive"))
      (node (ref "U$2") (pin "2") (pinfunction "P$2_2") (pintype "bidirectional"))
    )
    (net (code "27") (name "Net-(U$2-P$3)") (class "Default")
      (node (ref "J26") (pin "5") (pinfunction "5_5") (pintype "passive"))
      (node (ref "U$2") (pin "3") (pinfunction "P$3_3") (pintype "bidirectional"))
    )
    (net (code "28") (name "Net-(U$2-P$4)") (class "Default")
      (node (ref "J26") (pin "4") (pinfunction "4_4") (pintype "passive"))
      (node (ref "U$2") (pin "4") (pinfunction "P$4_4") (pintype "bidirectional"))
    )
    (net (code "29") (name "Net-(U$2-P$5)") (class "Default")
      (node (ref "J26") (pin "3") (pinfunction "3_3") (pintype "passive"))
      (node (ref "U$2") (pin "5") (pinfunction "P$5_5") (pintype "bidirectional"))
    )
    (net (code "30") (name "Net-(U$2-P$6)") (class "Default")
      (node (ref "J26") (pin "2") (pinfunction "2_2") (pintype "passive"))
      (node (ref "U$2") (pin "6") (pinfunction "P$6_6") (pintype "bidirectional"))
    )
    (net (code "31") (name "Net-(U$2-P$7)") (class "Default")
      (node (ref "J26") (pin "1") (pinfunction "1_1") (pintype "passive"))
      (node (ref "U$2") (pin "7") (pinfunction "P$7_7") (pintype "bidirectional"))
    )
    (net (code "32") (name "Net-(U$3-P$1)") (class "Default")
      (node (ref "J27") (pin "9") (pinfunction "9_9") (pintype "passive"))
      (node (ref "U$3") (pin "PIN1") (pinfunction "P$1_PIN1") (pintype "bidirectional"))
    )
    (net (code "33") (name "Net-(U$3-P$2)") (class "Default")
      (node (ref "J27") (pin "8") (pinfunction "8_8") (pintype "passive"))
      (node (ref "U$3") (pin "PIN2") (pinfunction "P$2_PIN2") (pintype "bidirectional"))
    )
    (net (code "34") (name "Net-(U$3-P$3)") (class "Default")
      (node (ref "J27") (pin "7") (pinfunction "7_7") (pintype "passive"))
      (node (ref "U$3") (pin "PIN3") (pinfunction "P$3_PIN3") (pintype "bidirectional"))
    )
    (net (code "35") (name "Net-(U$3-P$4)") (class "Default")
      (node (ref "J27") (pin "6") (pinfunction "6_6") (pintype "passive"))
      (node (ref "U$3") (pin "PIN4") (pinfunction "P$4_PIN4") (pintype "bidirectional"))
    )
    (net (code "36") (name "Net-(U$3-P$5)") (class "Default")
      (node (ref "J27") (pin "5") (pinfunction "5_5") (pintype "passive"))
      (node (ref "U$3") (pin "PIN5") (pinfunction "P$5_PIN5") (pintype "bidirectional"))
    )
    (net (code "37") (name "Net-(U$3-P$6)") (class "Default")
      (node (ref "J27") (pin "4") (pinfunction "4_4") (pintype "passive"))
      (node (ref "U$3") (pin "PIN6") (pinfunction "P$6_PIN6") (pintype "bidirectional"))
    )
    (net (code "38") (name "Net-(U$3-P$7)") (class "Default")
      (node (ref "J27") (pin "3") (pinfunction "3_3") (pintype "passive"))
      (node (ref "U$3") (pin "PIN7") (pinfunction "P$7_PIN7") (pintype "bidirectional"))
    )
    (net (code "39") (name "Net-(U$3-P$8)") (class "Default")
      (node (ref "J27") (pin "2") (pinfunction "2_2") (pintype "passive"))
      (node (ref "U$3") (pin "PIN8") (pinfunction "P$8_PIN8") (pintype "bidirectional"))
    )
    (net (code "40") (name "Net-(U$3-P$9)") (class "Default")
      (node (ref "J27") (pin "1") (pinfunction "1_1") (pintype "passive"))
      (node (ref "U$3") (pin "PIN9") (pinfunction "P$9_PIN9") (pintype "bidirectional"))
    )
    (net (code "41") (name "Net-(U$4-P$1)") (class "Default")
      (node (ref "J28") (pin "7") (pinfunction "7_7") (pintype "passive"))
      (node (ref "U$4") (pin "1") (pinfunction "P$1_1") (pintype "bidirectional"))
    )
    (net (code "42") (name "Net-(U$4-P$2)") (class "Default")
      (node (ref "J28") (pin "6") (pinfunction "6_6") (pintype "passive"))
      (node (ref "U$4") (pin "2") (pinfunction "P$2_2") (pintype "bidirectional"))
    )
    (net (code "43") (name "Net-(U$4-P$3)") (class "Default")
      (node (ref "J28") (pin "5") (pinfunction "5_5") (pintype "passive"))
      (node (ref "U$4") (pin "3") (pinfunction "P$3_3") (pintype "bidirectional"))
    )
    (net (code "44") (name "Net-(U$4-P$4)") (class "Default")
      (node (ref "J28") (pin "4") (pinfunction "4_4") (pintype "passive"))
      (node (ref "U$4") (pin "4") (pinfunction "P$4_4") (pintype "bidirectional"))
    )
    (net (code "45") (name "Net-(U$4-P$5)") (class "Default")
      (node (ref "J28") (pin "3") (pinfunction "3_3") (pintype "passive"))
      (node (ref "U$4") (pin "5") (pinfunction "P$5_5") (pintype "bidirectional"))
    )
    (net (code "46") (name "Net-(U$4-P$6)") (class "Default")
      (node (ref "J28") (pin "2") (pinfunction "2_2") (pintype "passive"))
      (node (ref "U$4") (pin "6") (pinfunction "P$6_6") (pintype "bidirectional"))
    )
    (net (code "47") (name "Net-(U$4-P$7)") (class "Default")
      (node (ref "J28") (pin "1") (pinfunction "1_1") (pintype "passive"))
      (node (ref "U$4") (pin "7") (pinfunction "P$7_7") (pintype "bidirectional"))
    )
    (net (code "48") (name "Net-(U$5-P$1)") (class "Default")
      (node (ref "J29") (pin "9") (pinfunction "9_9") (pintype "passive"))
      (node (ref "U$5") (pin "PIN1") (pinfunction "P$1_PIN1") (pintype "bidirectional"))
    )
    (net (code "49") (name "Net-(U$5-P$2)") (class "Default")
      (node (ref "J29") (pin "8") (pinfunction "8_8") (pintype "passive"))
      (node (ref "U$5") (pin "PIN2") (pinfunction "P$2_PIN2") (pintype "bidirectional"))
    )
    (net (code "50") (name "Net-(U$5-P$3)") (class "Default")
      (node (ref "J29") (pin "7") (pinfunction "7_7") (pintype "passive"))
      (node (ref "U$5") (pin "PIN3") (pinfunction "P$3_PIN3") (pintype "bidirectional"))
    )
    (net (code "51") (name "Net-(U$5-P$4)") (class "Default")
      (node (ref "J29") (pin "6") (pinfunction "6_6") (pintype "passive"))
      (node (ref "U$5") (pin "PIN4") (pinfunction "P$4_PIN4") (pintype "bidirectional"))
    )
    (net (code "52") (name "Net-(U$5-P$5)") (class "Default")
      (node (ref "J29") (pin "5") (pinfunction "5_5") (pintype "passive"))
      (node (ref "U$5") (pin "PIN5") (pinfunction "P$5_PIN5") (pintype "bidirectional"))
    )
    (net (code "53") (name "Net-(U$5-P$6)") (class "Default")
      (node (ref "J29") (pin "4") (pinfunction "4_4") (pintype "passive"))
      (node (ref "U$5") (pin "PIN6") (pinfunction "P$6_PIN6") (pintype "bidirectional"))
    )
    (net (code "54") (name "Net-(U$5-P$7)") (class "Default")
      (node (ref "J29") (pin "3") (pinfunction "3_3") (pintype "passive"))
      (node (ref "U$5") (pin "PIN7") (pinfunction "P$7_PIN7") (pintype "bidirectional"))
    )
    (net (code "55") (name "Net-(U$5-P$8)") (class "Default")
      (node (ref "J29") (pin "2") (pinfunction "2_2") (pintype "passive"))
      (node (ref "U$5") (pin "PIN8") (pinfunction "P$8_PIN8") (pintype "bidirectional"))
    )
    (net (code "56") (name "Net-(U$5-P$9)") (class "Default")
      (node (ref "J29") (pin "1") (pinfunction "1_1") (pintype "passive"))
      (node (ref "U$5") (pin "PIN9") (pinfunction "P$9_PIN9") (pintype "bidirectional"))
    )
    (net (code "57") (name "Net-(U$6-P$1)") (class "Default")
      (node (ref "J30") (pin "7") (pinfunction "7_7") (pintype "passive"))
      (node (ref "U$6") (pin "1") (pinfunction "P$1_1") (pintype "bidirectional"))
    )
    (net (code "58") (name "Net-(U$6-P$2)") (class "Default")
      (node (ref "J30") (pin "6") (pinfunction "6_6") (pintype "passive"))
      (node (ref "U$6") (pin "2") (pinfunction "P$2_2") (pintype "bidirectional"))
    )
    (net (code "59") (name "Net-(U$6-P$3)") (class "Default")
      (node (ref "J30") (pin "5") (pinfunction "5_5") (pintype "passive"))
      (node (ref "U$6") (pin "3") (pinfunction "P$3_3") (pintype "bidirectional"))
    )
    (net (code "60") (name "Net-(U$6-P$4)") (class "Default")
      (node (ref "J30") (pin "4") (pinfunction "4_4") (pintype "passive"))
      (node (ref "U$6") (pin "4") (pinfunction "P$4_4") (pintype "bidirectional"))
    )
    (net (code "61") (name "Net-(U$6-P$5)") (class "Default")
      (node (ref "J30") (pin "3") (pinfunction "3_3") (pintype "passive"))
      (node (ref "U$6") (pin "5") (pinfunction "P$5_5") (pintype "bidirectional"))
    )
    (net (code "62") (name "Net-(U$6-P$6)") (class "Default")
      (node (ref "J30") (pin "2") (pinfunction "2_2") (pintype "passive"))
      (node (ref "U$6") (pin "6") (pinfunction "P$6_6") (pintype "bidirectional"))
    )
    (net (code "63") (name "Net-(U$6-P$7)") (class "Default")
      (node (ref "J30") (pin "1") (pinfunction "1_1") (pintype "passive"))
      (node (ref "U$6") (pin "7") (pinfunction "P$7_7") (pintype "bidirectional"))
    )
    (net (code "64") (name "Net-(U$7-P$1)") (class "Default")
      (node (ref "J35") (pin "7") (pinfunction "7_7") (pintype "passive"))
      (node (ref "U$7") (pin "1") (pinfunction "P$1_1") (pintype "bidirectional"))
    )
    (net (code "65") (name "Net-(U$7-P$2)") (class "Default")
      (node (ref "J35") (pin "6") (pinfunction "6_6") (pintype "passive"))
      (node (ref "U$7") (pin "2") (pinfunction "P$2_2") (pintype "bidirectional"))
    )
    (net (code "66") (name "Net-(U$7-P$3)") (class "Default")
      (node (ref "J35") (pin "5") (pinfunction "5_5") (pintype "passive"))
      (node (ref "U$7") (pin "3") (pinfunction "P$3_3") (pintype "bidirectional"))
    )
    (net (code "67") (name "Net-(U$7-P$4)") (class "Default")
      (node (ref "J35") (pin "4") (pinfunction "4_4") (pintype "passive"))
      (node (ref "U$7") (pin "4") (pinfunction "P$4_4") (pintype "bidirectional"))
    )
    (net (code "68") (name "Net-(U$7-P$5)") (class "Default")
      (node (ref "J35") (pin "3") (pinfunction "3_3") (pintype "passive"))
      (node (ref "U$7") (pin "5") (pinfunction "P$5_5") (pintype "bidirectional"))
    )
    (net (code "69") (name "Net-(U$7-P$6)") (class "Default")
      (node (ref "J35") (pin "2") (pinfunction "2_2") (pintype "passive"))
      (node (ref "U$7") (pin "6") (pinfunction "P$6_6") (pintype "bidirectional"))
    )
    (net (code "70") (name "Net-(U$7-P$7)") (class "Default")
      (node (ref "J35") (pin "1") (pinfunction "1_1") (pintype "passive"))
      (node (ref "U$7") (pin "7") (pinfunction "P$7_7") (pintype "bidirectional"))
    )
    (net (code "71") (name "Net-(U$8-P$1)") (class "Default")
      (node (ref "J32") (pin "9") (pinfunction "9_9") (pintype "passive"))
      (node (ref "U$8") (pin "PIN1") (pinfunction "P$1_PIN1") (pintype "bidirectional"))
    )
    (net (code "72") (name "Net-(U$8-P$2)") (class "Default")
      (node (ref "J32") (pin "8") (pinfunction "8_8") (pintype "passive"))
      (node (ref "U$8") (pin "PIN2") (pinfunction "P$2_PIN2") (pintype "bidirectional"))
    )
    (net (code "73") (name "Net-(U$8-P$3)") (class "Default")
      (node (ref "J32") (pin "7") (pinfunction "7_7") (pintype "passive"))
      (node (ref "U$8") (pin "PIN3") (pinfunction "P$3_PIN3") (pintype "bidirectional"))
    )
    (net (code "74") (name "Net-(U$8-P$4)") (class "Default")
      (node (ref "J32") (pin "6") (pinfunction "6_6") (pintype "passive"))
      (node (ref "U$8") (pin "PIN4") (pinfunction "P$4_PIN4") (pintype "bidirectional"))
    )
    (net (code "75") (name "Net-(U$8-P$5)") (class "Default")
      (node (ref "J32") (pin "5") (pinfunction "5_5") (pintype "passive"))
      (node (ref "U$8") (pin "PIN5") (pinfunction "P$5_PIN5") (pintype "bidirectional"))
    )
    (net (code "76") (name "Net-(U$8-P$6)") (class "Default")
      (node (ref "J32") (pin "4") (pinfunction "4_4") (pintype "passive"))
      (node (ref "U$8") (pin "PIN6") (pinfunction "P$6_PIN6") (pintype "bidirectional"))
    )
    (net (code "77") (name "Net-(U$8-P$7)") (class "Default")
      (node (ref "J32") (pin "3") (pinfunction "3_3") (pintype "passive"))
      (node (ref "U$8") (pin "PIN7") (pinfunction "P$7_PIN7") (pintype "bidirectional"))
    )
    (net (code "78") (name "Net-(U$8-P$8)") (class "Default")
      (node (ref "J32") (pin "2") (pinfunction "2_2") (pintype "passive"))
      (node (ref "U$8") (pin "PIN8") (pinfunction "P$8_PIN8") (pintype "bidirectional"))
    )
    (net (code "79") (name "Net-(U$8-P$9)") (class "Default")
      (node (ref "J32") (pin "1") (pinfunction "1_1") (pintype "passive"))
      (node (ref "U$8") (pin "PIN9") (pinfunction "P$9_PIN9") (pintype "bidirectional"))
    )
    (net (code "80") (name "Net-(U$9-P$1)") (class "Default")
      (node (ref "J33") (pin "7") (pinfunction "7_7") (pintype "passive"))
      (node (ref "U$9") (pin "1") (pinfunction "P$1_1") (pintype "bidirectional"))
    )
    (net (code "81") (name "Net-(U$9-P$2)") (class "Default")
      (node (ref "J33") (pin "6") (pinfunction "6_6") (pintype "passive"))
      (node (ref "U$9") (pin "2") (pinfunction "P$2_2") (pintype "bidirectional"))
    )
    (net (code "82") (name "Net-(U$9-P$3)") (class "Default")
      (node (ref "J33") (pin "5") (pinfunction "5_5") (pintype "passive"))
      (node (ref "U$9") (pin "3") (pinfunction "P$3_3") (pintype "bidirectional"))
    )
    (net (code "83") (name "Net-(U$9-P$4)") (class "Default")
      (node (ref "J33") (pin "4") (pinfunction "4_4") (pintype "passive"))
      (node (ref "U$9") (pin "4") (pinfunction "P$4_4") (pintype "bidirectional"))
    )
    (net (code "84") (name "Net-(U$9-P$5)") (class "Default")
      (node (ref "J33") (pin "3") (pinfunction "3_3") (pintype "passive"))
      (node (ref "U$9") (pin "5") (pinfunction "P$5_5") (pintype "bidirectional"))
    )
    (net (code "85") (name "Net-(U$9-P$6)") (class "Default")
      (node (ref "J33") (pin "2") (pinfunction "2_2") (pintype "passive"))
      (node (ref "U$9") (pin "6") (pinfunction "P$6_6") (pintype "bidirectional"))
    )
    (net (code "86") (name "Net-(U$9-P$7)") (class "Default")
      (node (ref "J33") (pin "1") (pinfunction "1_1") (pintype "passive"))
      (node (ref "U$9") (pin "7") (pinfunction "P$7_7") (pintype "bidirectional"))
    )
    (net (code "87") (name "Net-(U$10-P$1)") (class "Default")
      (node (ref "J34") (pin "9") (pinfunction "9_9") (pintype "passive"))
      (node (ref "U$10") (pin "PIN1") (pinfunction "P$1_PIN1") (pintype "bidirectional"))
    )
    (net (code "88") (name "Net-(U$10-P$2)") (class "Default")
      (node (ref "J34") (pin "8") (pinfunction "8_8") (pintype "passive"))
      (node (ref "U$10") (pin "PIN2") (pinfunction "P$2_PIN2") (pintype "bidirectional"))
    )
    (net (code "89") (name "Net-(U$10-P$3)") (class "Default")
      (node (ref "J34") (pin "7") (pinfunction "7_7") (pintype "passive"))
      (node (ref "U$10") (pin "PIN3") (pinfunction "P$3_PIN3") (pintype "bidirectional"))
    )
    (net (code "90") (name "Net-(U$10-P$4)") (class "Default")
      (node (ref "J34") (pin "6") (pinfunction "6_6") (pintype "passive"))
      (node (ref "U$10") (pin "PIN4") (pinfunction "P$4_PIN4") (pintype "bidirectional"))
    )
    (net (code "91") (name "Net-(U$10-P$5)") (class "Default")
      (node (ref "J34") (pin "5") (pinfunction "5_5") (pintype "passive"))
      (node (ref "U$10") (pin "PIN5") (pinfunction "P$5_PIN5") (pintype "bidirectional"))
    )
    (net (code "92") (name "Net-(U$10-P$6)") (class "Default")
      (node (ref "J34") (pin "4") (pinfunction "4_4") (pintype "passive"))
      (node (ref "U$10") (pin "PIN6") (pinfunction "P$6_PIN6") (pintype "bidirectional"))
    )
    (net (code "93") (name "Net-(U$10-P$7)") (class "Default")
      (node (ref "J34") (pin "3") (pinfunction "3_3") (pintype "passive"))
      (node (ref "U$10") (pin "PIN7") (pinfunction "P$7_PIN7") (pintype "bidirectional"))
    )
    (net (code "94") (name "Net-(U$10-P$8)") (class "Default")
      (node (ref "J34") (pin "2") (pinfunction "2_2") (pintype "passive"))
      (node (ref "U$10") (pin "PIN8") (pinfunction "P$8_PIN8") (pintype "bidirectional"))
    )
    (net (code "95") (name "Net-(U$10-P$9)") (class "Default")
      (node (ref "J34") (pin "1") (pinfunction "1_1") (pintype "passive"))
      (node (ref "U$10") (pin "PIN9") (pinfunction "P$9_PIN9") (pintype "bidirectional"))
    )
    (net (code "96") (name "Net-(U$11-P$1)") (class "Default")
      (node (ref "J31") (pin "7") (pinfunction "7_7") (pintype "passive"))
      (node (ref "U$11") (pin "1") (pinfunction "P$1_1") (pintype "bidirectional"))
    )
    (net (code "97") (name "Net-(U$11-P$2)") (class "Default")
      (node (ref "J31") (pin "6") (pinfunction "6_6") (pintype "passive"))
      (node (ref "U$11") (pin "2") (pinfunction "P$2_2") (pintype "bidirectional"))
    )
    (net (code "98") (name "Net-(U$11-P$3)") (class "Default")
      (node (ref "J31") (pin "5") (pinfunction "5_5") (pintype "passive"))
      (node (ref "U$11") (pin "3") (pinfunction "P$3_3") (pintype "bidirectional"))
    )
    (net (code "99") (name "Net-(U$11-P$4)") (class "Default")
      (node (ref "J31") (pin "4") (pinfunction "4_4") (pintype "passive"))
      (node (ref "U$11") (pin "4") (pinfunction "P$4_4") (pintype "bidirectional"))
    )
    (net (code "100") (name "Net-(U$11-P$5)") (class "Default")
      (node (ref "J31") (pin "3") (pinfunction "3_3") (pintype "passive"))
      (node (ref "U$11") (pin "5") (pinfunction "P$5_5") (pintype "bidirectional"))
    )
    (net (code "101") (name "Net-(U$11-P$6)") (class "Default")
      (node (ref "J31") (pin "2") (pinfunction "2_2") (pintype "passive"))
      (node (ref "U$11") (pin "6") (pinfunction "P$6_6") (pintype "bidirectional"))
    )
    (net (code "102") (name "Net-(U$11-P$7)") (class "Default")
      (node (ref "J31") (pin "1") (pinfunction "1_1") (pintype "passive"))
      (node (ref "U$11") (pin "7") (pinfunction "P$7_7") (pintype "bidirectional"))
    )
    (net (code "103") (name "Net-(U$12-P$1)") (class "Default")
      (node (ref "J36") (pin "9") (pinfunction "9_9") (pintype "passive"))
      (node (ref "U$12") (pin "PIN1") (pinfunction "P$1_PIN1") (pintype "bidirectional"))
    )
    (net (code "104") (name "Net-(U$12-P$2)") (class "Default")
      (node (ref "J36") (pin "8") (pinfunction "8_8") (pintype "passive"))
      (node (ref "U$12") (pin "PIN2") (pinfunction "P$2_PIN2") (pintype "bidirectional"))
    )
    (net (code "105") (name "Net-(U$12-P$3)") (class "Default")
      (node (ref "J36") (pin "7") (pinfunction "7_7") (pintype "passive"))
      (node (ref "U$12") (pin "PIN3") (pinfunction "P$3_PIN3") (pintype "bidirectional"))
    )
    (net (code "106") (name "Net-(U$12-P$4)") (class "Default")
      (node (ref "J36") (pin "6") (pinfunction "6_6") (pintype "passive"))
      (node (ref "U$12") (pin "PIN4") (pinfunction "P$4_PIN4") (pintype "bidirectional"))
    )
    (net (code "107") (name "Net-(U$12-P$5)") (class "Default")
      (node (ref "J36") (pin "5") (pinfunction "5_5") (pintype "passive"))
      (node (ref "U$12") (pin "PIN5") (pinfunction "P$5_PIN5") (pintype "bidirectional"))
    )
    (net (code "108") (name "Net-(U$12-P$6)") (class "Default")
      (node (ref "J36") (pin "4") (pinfunction "4_4") (pintype "passive"))
      (node (ref "U$12") (pin "PIN6") (pinfunction "P$6_PIN6") (pintype "bidirectional"))
    )
    (net (code "109") (name "Net-(U$12-P$7)") (class "Default")
      (node (ref "J36") (pin "3") (pinfunction "3_3") (pintype "passive"))
      (node (ref "U$12") (pin "PIN7") (pinfunction "P$7_PIN7") (pintype "bidirectional"))
    )
    (net (code "110") (name "Net-(U$12-P$8)") (class "Default")
      (node (ref "J36") (pin "2") (pinfunction "2_2") (pintype "passive"))
      (node (ref "U$12") (pin "PIN8") (pinfunction "P$8_PIN8") (pintype "bidirectional"))
    )
    (net (code "111") (name "Net-(U$12-P$9)") (class "Default")
      (node (ref "J36") (pin "1") (pinfunction "1_1") (pintype "passive"))
      (node (ref "U$12") (pin "PIN9") (pinfunction "P$9_PIN9") (pintype "bidirectional"))
    )
  )
)
